# EVsimv2.net
KiCad netlist of a schematic drawn in EAGLE
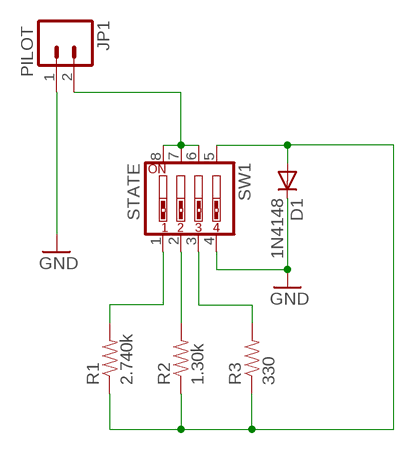
[diagram p0: schematic, sheet 1]

(export (version "E")
  (design (tool "Eeschema 10.0.6"))
  (components
    (comp (ref "D1")
      (value "1N4148")
      (footprint "eagle-import:DIODE-1N4148")
      (libsource (lib "eagle-import") (part "DIODE1N4148"))
    )
    (comp (ref "JP1")
      (value "PILOT")
      (footprint "eagle-import:SCREWTERMINAL-3.5MM-2_LOCK")
      (libsource (lib "eagle-import") (part "M023.5MM_LOCK"))
    )
    (comp (ref "R1")
      (value "2.740k")
      (footprint "eagle-import:AXIAL-0.4")
      (libsource (lib "eagle-import") (part "RESISTORPTH-1/4W"))
    )
    (comp (ref "R2")
      (value "1.30k")
      (footprint "eagle-import:AXIAL-0.4")
      (libsource (lib "eagle-import") (part "RESISTORPTH-1/4W"))
    )
    (comp (ref "R3")
      (value "330")
      (footprint "eagle-import:AXIAL-0.4")
      (libsource (lib "eagle-import") (part "RESISTORPTH-1/4W"))
    )
    (comp (ref "SW1")
      (value "STATE")
      (footprint "eagle-import:EDG-04")
      (libsource (lib "eagle-import") (part "SW_DIP-4"))
    )
  )
  (nets
    (net (code "1") (name "GND") (class "Default")
      (node (ref "D1") (pin "C") (pinfunction "C_C") (pintype "passive"))
      (node (ref "JP1") (pin "1") (pinfunction "1_1") (pintype "passive"))
      (node (ref "SW1") (pin "4") (pinfunction "4_4") (pintype "passive"))
    )
    (net (code "2") (name "Net-(JP1-Pad2)") (class "Default")
      (node (ref "JP1") (pin "2") (pinfunction "2_2") (pintype "passive"))
      (node (ref "SW1") (pin "6") (pinfunction "6_6") (pintype "passive"))
      (node (ref "SW1") (pin "7") (pinfunction "7_7") (pintype "passive"))
      (node (ref "SW1") (pin "8") (pinfunction "8_8") (pintype "passive"))
    )
    (net (code "3") (name "Net-(R1-1)") (class "Default")
      (node (ref "D1") (pin "A") (pinfunction "A_A") (pintype "passive"))
      (node (ref "R1") (pin "P$1") (pinfunction "1_P$1") (pintype "passive"))
      (node (ref "R2") (pin "P$1") (pinfunction "1_P$1") (pintype "passive"))
      (node (ref "R3") (pin "P$1") (pinfunction "1_P$1") (pintype "passive"))
      (node (ref "SW1") (pin "5") (pinfunction "5_5") (pintype "passive"))
    )
    (net (code "4") (name "Net-(R1-2)") (class "Default")
      (node (ref "R1") (pin "P$2") (pinfunction "2_P$2") (pintype "passive"))
      (node (ref "SW1") (pin "1") (pinfunction "1_1") (pintype "passive"))
    )
    (net (code "5") (name "Net-(R2-2)") (class "Default")
      (node (ref "R2") (pin "P$2") (pinfunction "2_P$2") (pintype "passive"))
      (node (ref "SW1") (pin "2") (pinfunction "2_2") (pintype "passive"))
    )
    (net (code "6") (name "Net-(R3-2)") (class "Default")
      (node (ref "R3") (pin "P$2") (pinfunction "2_P$2") (pintype "passive"))
      (node (ref "SW1") (pin "3") (pinfunction "3_3") (pintype "passive"))
    )
  )
)
